# base_1.net
KiCad netlist of a schematic drawn in EAGLE
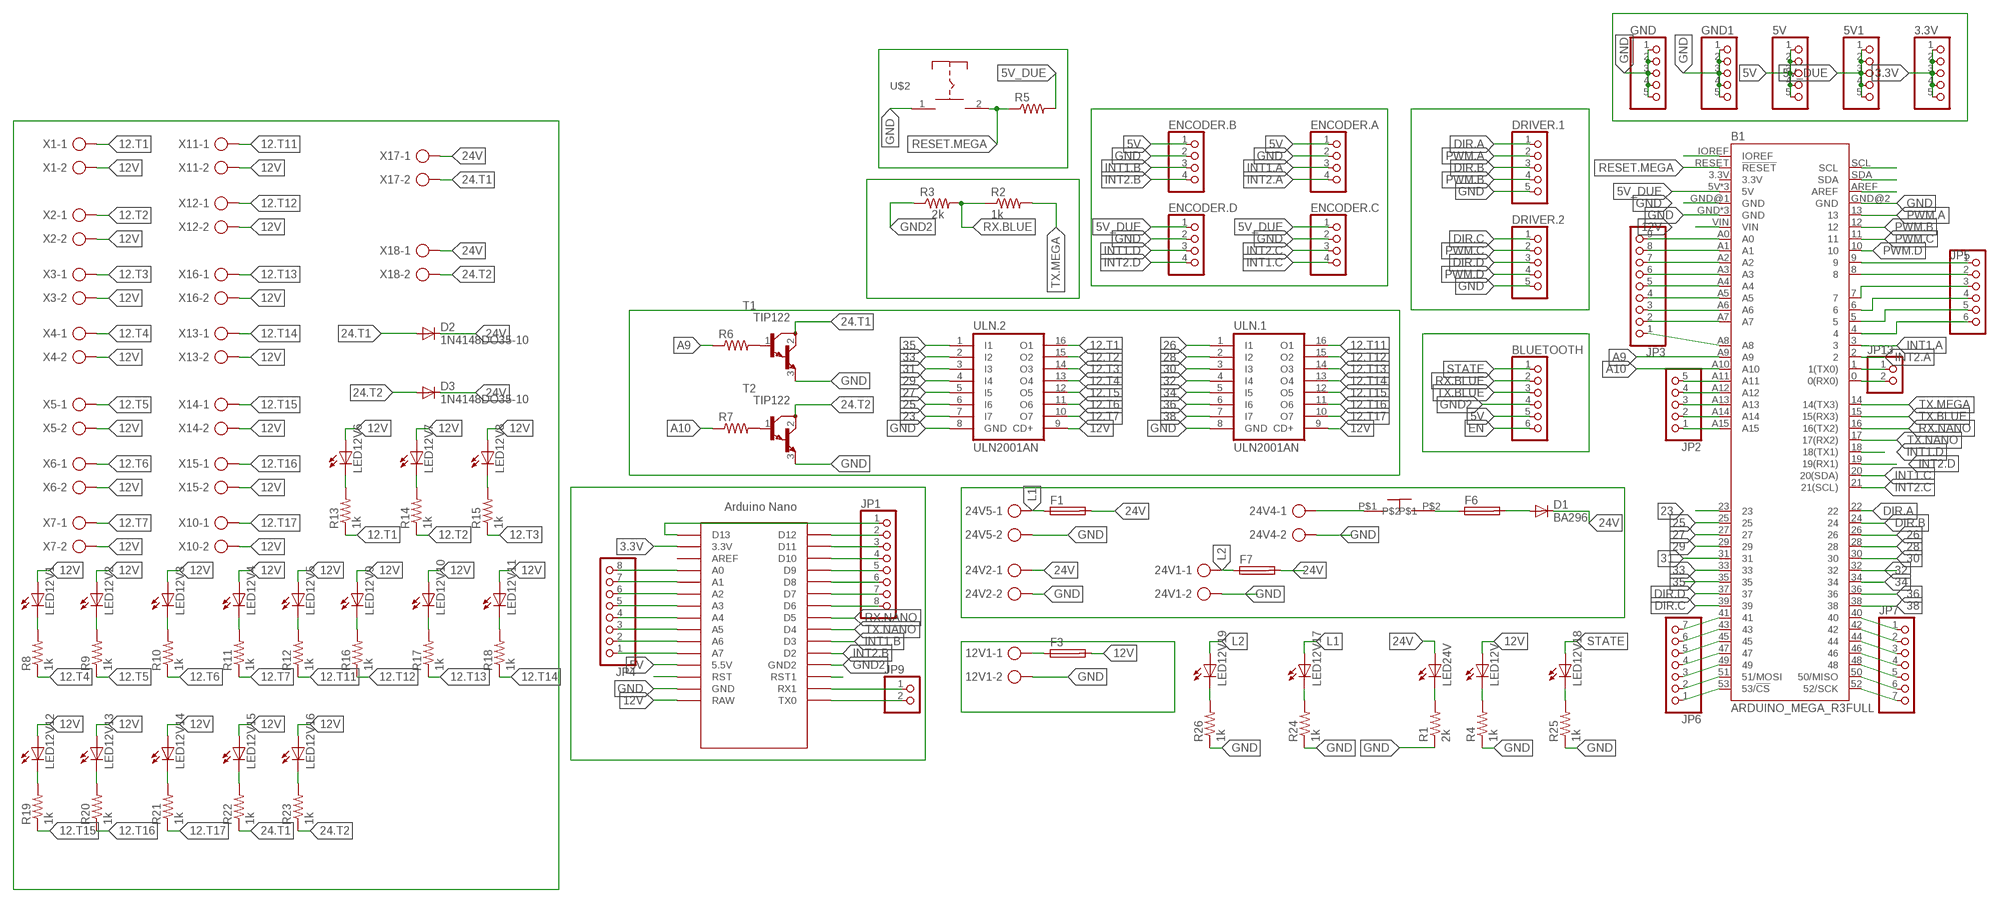
[diagram p0: schematic, sheet 1]

(export (version "E")
  (design (tool "Eeschema 10.0.6"))
  (components
    (comp (ref "3.3V")
      (value "PINHD-1X5")
      (footprint "eagle-import:1X05")
      (libsource (lib "eagle-import") (part "PINHD-1X5"))
    )
    (comp (ref "5V")
      (value "PINHD-1X5")
      (footprint "eagle-import:1X05")
      (libsource (lib "eagle-import") (part "PINHD-1X5"))
    )
    (comp (ref "5V1")
      (value "PINHD-1X5")
      (footprint "eagle-import:1X05")
      (libsource (lib "eagle-import") (part "PINHD-1X5"))
    )
    (comp (ref "12V1")
      (value "AK300/2")
      (footprint "eagle-import:AK300_2")
      (libsource (lib "eagle-import") (part "AK300/2"))
    )
    (comp (ref "24V1")
      (value "AK300/2")
      (footprint "eagle-import:AK300_2")
      (libsource (lib "eagle-import") (part "AK300/2"))
    )
    (comp (ref "24V2")
      (value "AK300/2")
      (footprint "eagle-import:AK300_2")
      (libsource (lib "eagle-import") (part "AK300/2"))
    )
    (comp (ref "24V4")
      (value "W237-113")
      (footprint "eagle-import:W237-113")
      (libsource (lib "eagle-import") (part "W237-113"))
    )
    (comp (ref "24V5")
      (value "AK300/2")
      (footprint "eagle-import:AK300_2")
      (libsource (lib "eagle-import") (part "AK300/2"))
    )
    (comp (ref "B1")
      (value "ARDUINO_MEGA_R3FULL")
      (footprint "eagle-import:ARDUINO_MEGA_NO_SILK")
      (libsource (lib "eagle-import") (part "ARDUINO_MEGA_R3FULL"))
    )
    (comp (ref "BLUETOOTH")
      (value "PINHD-1X6")
      (footprint "eagle-import:1X06")
      (libsource (lib "eagle-import") (part "PINHD-1X6"))
    )
    (comp (ref "D1")
      (value "BA296")
      (footprint "eagle-import:P2-15")
      (libsource (lib "eagle-import") (part "BA296"))
    )
    (comp (ref "D2")
      (value "1N4148DO35-10")
      (footprint "eagle-import:DO35-10")
      (libsource (lib "eagle-import") (part "1N4148DO35-10"))
    )
    (comp (ref "D3")
      (value "1N4148DO35-10")
      (footprint "eagle-import:DO35-10")
      (libsource (lib "eagle-import") (part "1N4148DO35-10"))
    )
    (comp (ref "DRIVER.1")
      (value "PINHD-1X5")
      (footprint "eagle-import:1X05")
      (libsource (lib "eagle-import") (part "PINHD-1X5"))
    )
    (comp (ref "DRIVER.2")
      (value "PINHD-1X5")
      (footprint "eagle-import:1X05")
      (libsource (lib "eagle-import") (part "PINHD-1X5"))
    )
    (comp (ref "ENCODER.A")
      (value "PINHD-1X4")
      (footprint "eagle-import:1X04")
      (libsource (lib "eagle-import") (part "PINHD-1X4"))
    )
    (comp (ref "ENCODER.B")
      (value "PINHD-1X4")
      (footprint "eagle-import:1X04")
      (libsource (lib "eagle-import") (part "PINHD-1X4"))
    )
    (comp (ref "ENCODER.C")
      (value "PINHD-1X4")
      (footprint "eagle-import:1X04")
      (libsource (lib "eagle-import") (part "PINHD-1X4"))
    )
    (comp (ref "ENCODER.D")
      (value "PINHD-1X4")
      (footprint "eagle-import:1X04")
      (libsource (lib "eagle-import") (part "PINHD-1X4"))
    )
    (comp (ref "F1")
      (value "SH22,5A")
      (footprint "eagle-import:SH22,5A")
      (fields (field (name "MPN") "0031.7701.11"))
      (libsource (lib "eagle-import") (part "SH22,5A"))
    )
    (comp (ref "F3")
      (value "SH22,5A")
      (footprint "eagle-import:SH22,5A")
      (fields (field (name "MPN") "0031.7701.11"))
      (libsource (lib "eagle-import") (part "SH22,5A"))
    )
    (comp (ref "F6")
      (value "SH22,5A")
      (footprint "eagle-import:SH22,5A")
      (fields (field (name "MPN") "0031.7701.11"))
      (libsource (lib "eagle-import") (part "SH22,5A"))
    )
    (comp (ref "F7")
      (value "SH22,5A")
      (footprint "eagle-import:SH22,5A")
      (fields (field (name "MPN") "0031.7701.11"))
      (libsource (lib "eagle-import") (part "SH22,5A"))
    )
    (comp (ref "GND")
      (value "PINHD-1X5")
      (footprint "eagle-import:1X05")
      (libsource (lib "eagle-import") (part "PINHD-1X5"))
    )
    (comp (ref "GND1")
      (value "PINHD-1X5")
      (footprint "eagle-import:1X05")
      (libsource (lib "eagle-import") (part "PINHD-1X5"))
    )
    (comp (ref "JP1")
      (value "PINHD-1X8")
      (footprint "eagle-import:1X08")
      (libsource (lib "eagle-import") (part "PINHD-1X8"))
    )
    (comp (ref "JP2")
      (value "PINHD-1X5")
      (footprint "eagle-import:1X05")
      (libsource (lib "eagle-import") (part "PINHD-1X5"))
    )
    (comp (ref "JP3")
      (value "PINHD-1X9")
      (footprint "eagle-import:1X09")
      (libsource (lib "eagle-import") (part "PINHD-1X9"))
    )
    (comp (ref "JP4")
      (value "PINHD-1X8")
      (footprint "eagle-import:1X08")
      (libsource (lib "eagle-import") (part "PINHD-1X8"))
    )
    (comp (ref "JP5")
      (value "PINHD-1X6")
      (footprint "eagle-import:1X06")
      (libsource (lib "eagle-import") (part "PINHD-1X6"))
    )
    (comp (ref "JP6")
      (value "PINHD-1X7")
      (footprint "eagle-import:1X07")
      (libsource (lib "eagle-import") (part "PINHD-1X7"))
    )
    (comp (ref "JP7")
      (value "PINHD-1X7")
      (footprint "eagle-import:1X07")
      (libsource (lib "eagle-import") (part "PINHD-1X7"))
    )
    (comp (ref "JP9")
      (value "PINHD-1X2")
      (footprint "eagle-import:1X02")
      (libsource (lib "eagle-import") (part "PINHD-1X2"))
    )
    (comp (ref "JP13")
      (value "PINHD-1X2")
      (footprint "eagle-import:1X02")
      (libsource (lib "eagle-import") (part "PINHD-1X2"))
    )
    (comp (ref "LED12V")
      (value "LED5MM")
      (footprint "eagle-import:LED5MM")
      (libsource (lib "eagle-import") (part "LED5MM"))
    )
    (comp (ref "LED12V1")
      (value "LED3MM")
      (footprint "eagle-import:LED3MM")
      (libsource (lib "eagle-import") (part "LED3MM"))
    )
    (comp (ref "LED12V2")
      (value "LED3MM")
      (footprint "eagle-import:LED3MM")
      (libsource (lib "eagle-import") (part "LED3MM"))
    )
    (comp (ref "LED12V3")
      (value "LED3MM")
      (footprint "eagle-import:LED3MM")
      (libsource (lib "eagle-import") (part "LED3MM"))
    )
    (comp (ref "LED12V4")
      (value "LED3MM")
      (footprint "eagle-import:LED3MM")
      (libsource (lib "eagle-import") (part "LED3MM"))
    )
    (comp (ref "LED12V5")
      (value "LED3MM")
      (footprint "eagle-import:LED3MM")
      (libsource (lib "eagle-import") (part "LED3MM"))
    )
    (comp (ref "LED12V6")
      (value "LED3MM")
      (footprint "eagle-import:LED3MM")
      (libsource (lib "eagle-import") (part "LED3MM"))
    )
    (comp (ref "LED12V7")
      (value "LED3MM")
      (footprint "eagle-import:LED3MM")
      (libsource (lib "eagle-import") (part "LED3MM"))
    )
    (comp (ref "LED12V8")
      (value "LED3MM")
      (footprint "eagle-import:LED3MM")
      (libsource (lib "eagle-import") (part "LED3MM"))
    )
    (comp (ref "LED12V9")
      (value "LED3MM")
      (footprint "eagle-import:LED3MM")
      (libsource (lib "eagle-import") (part "LED3MM"))
    )
    (comp (ref "LED12V10")
      (value "LED3MM")
      (footprint "eagle-import:LED3MM")
      (libsource (lib "eagle-import") (part "LED3MM"))
    )
    (comp (ref "LED12V11")
      (value "LED3MM")
      (footprint "eagle-import:LED3MM")
      (libsource (lib "eagle-import") (part "LED3MM"))
    )
    (comp (ref "LED12V12")
      (value "LED3MM")
      (footprint "eagle-import:LED3MM")
      (libsource (lib "eagle-import") (part "LED3MM"))
    )
    (comp (ref "LED12V13")
      (value "LED3MM")
      (footprint "eagle-import:LED3MM")
      (libsource (lib "eagle-import") (part "LED3MM"))
    )
    (comp (ref "LED12V14")
      (value "LED3MM")
      (footprint "eagle-import:LED3MM")
      (libsource (lib "eagle-import") (part "LED3MM"))
    )
    (comp (ref "LED12V15")
      (value "LED3MM")
      (footprint "eagle-import:LED3MM")
      (libsource (lib "eagle-import") (part "LED3MM"))
    )
    (comp (ref "LED12V16")
      (value "LED3MM")
      (footprint "eagle-import:LED3MM")
      (libsource (lib "eagle-import") (part "LED3MM"))
    )
    (comp (ref "LED12V17")
      (value "LED3MM")
      (footprint "eagle-import:LED3MM")
      (libsource (lib "eagle-import") (part "LED3MM"))
    )
    (comp (ref "LED12V18")
      (value "LED3MM")
      (footprint "eagle-import:LED3MM")
      (libsource (lib "eagle-import") (part "LED3MM"))
    )
    (comp (ref "LED12V19")
      (value "LED3MM")
      (footprint "eagle-import:LED3MM")
      (libsource (lib "eagle-import") (part "LED3MM"))
    )
    (comp (ref "LED24V")
      (value "LED5MM")
      (footprint "eagle-import:LED5MM")
      (libsource (lib "eagle-import") (part "LED5MM"))
    )
    (comp (ref "R1")
      (value "2k")
      (footprint "eagle-import:0207_10")
      (libsource (lib "eagle-import") (part "R-US_0207/10"))
    )
    (comp (ref "R2")
      (value "1k")
      (footprint "eagle-import:0204_7")
      (libsource (lib "eagle-import") (part "R-US_0204/7"))
    )
    (comp (ref "R3")
      (value "2k")
      (footprint "eagle-import:0207_10")
      (libsource (lib "eagle-import") (part "R-US_0207/10"))
    )
    (comp (ref "R4")
      (value "1k")
      (footprint "eagle-import:0207_10")
      (libsource (lib "eagle-import") (part "R-US_0207/10"))
    )
    (comp (ref "R5")
      (value "R-US_0207/12")
      (footprint "eagle-import:0207_12")
      (libsource (lib "eagle-import") (part "R-US_0207/12"))
    )
    (comp (ref "R6")
      (value "R-US_0204/5")
      (footprint "eagle-import:0204_5")
      (libsource (lib "eagle-import") (part "R-US_0204/5"))
    )
    (comp (ref "R7")
      (value "R-US_0204/5")
      (footprint "eagle-import:0204_5")
      (libsource (lib "eagle-import") (part "R-US_0204/5"))
    )
    (comp (ref "R8")
      (value "1k")
      (footprint "eagle-import:0204_5")
      (libsource (lib "eagle-import") (part "R-US_0204/5"))
    )
    (comp (ref "R9")
      (value "1k")
      (footprint "eagle-import:0204_5")
      (libsource (lib "eagle-import") (part "R-US_0204/5"))
    )
    (comp (ref "R10")
      (value "1k")
      (footprint "eagle-import:0204_5")
      (libsource (lib "eagle-import") (part "R-US_0204/5"))
    )
    (comp (ref "R11")
      (value "1k")
      (footprint "eagle-import:0204_5")
      (libsource (lib "eagle-import") (part "R-US_0204/5"))
    )
    (comp (ref "R12")
      (value "1k")
      (footprint "eagle-import:0204_5")
      (libsource (lib "eagle-import") (part "R-US_0204/5"))
    )
    (comp (ref "R13")
      (value "1k")
      (footprint "eagle-import:0204_5")
      (libsource (lib "eagle-import") (part "R-US_0204/5"))
    )
    (comp (ref "R14")
      (value "1k")
      (footprint "eagle-import:0204_5")
      (libsource (lib "eagle-import") (part "R-US_0204/5"))
    )
    (comp (ref "R15")
      (value "1k")
      (footprint "eagle-import:0204_5")
      (libsource (lib "eagle-import") (part "R-US_0204/5"))
    )
    (comp (ref "R16")
      (value "1k")
      (footprint "eagle-import:0204_5")
      (libsource (lib "eagle-import") (part "R-US_0204/5"))
    )
    (comp (ref "R17")
      (value "1k")
      (footprint "eagle-import:0204_5")
      (libsource (lib "eagle-import") (part "R-US_0204/5"))
    )
    (comp (ref "R18")
      (value "1k")
      (footprint "eagle-import:0204_5")
      (libsource (lib "eagle-import") (part "R-US_0204/5"))
    )
    (comp (ref "R19")
      (value "1k")
      (footprint "eagle-import:0204_5")
      (libsource (lib "eagle-import") (part "R-US_0204/5"))
    )
    (comp (ref "R20")
      (value "1k")
      (footprint "eagle-import:0204_5")
      (libsource (lib "eagle-import") (part "R-US_0204/5"))
    )
    (comp (ref "R21")
      (value "1k")
      (footprint "eagle-import:0204_5")
      (libsource (lib "eagle-import") (part "R-US_0204/5"))
    )
    (comp (ref "R22")
      (value "1k")
      (footprint "eagle-import:0204_5")
      (libsource (lib "eagle-import") (part "R-US_0204/5"))
    )
    (comp (ref "R23")
      (value "1k")
      (footprint "eagle-import:0204_5")
      (libsource (lib "eagle-import") (part "R-US_0204/5"))
    )
    (comp (ref "R24")
      (value "1k")
      (footprint "eagle-import:0204_5")
      (libsource (lib "eagle-import") (part "R-US_0204/5"))
    )
    (comp (ref "R25")
      (value "1k")
      (footprint "eagle-import:0204_5")
      (libsource (lib "eagle-import") (part "R-US_0204/5"))
    )
    (comp (ref "R26")
      (value "1k")
      (footprint "eagle-import:0204_5")
      (libsource (lib "eagle-import") (part "R-US_0204/5"))
    )
    (comp (ref "T1")
      (value "TIP122")
      (footprint "eagle-import:TO220")
      (libsource (lib "eagle-import") (part "TIP122"))
    )
    (comp (ref "T2")
      (value "TIP122")
      (footprint "eagle-import:TO220")
      (libsource (lib "eagle-import") (part "TIP122"))
    )
    (comp (ref "U$1")
      (value "NANO")
      (footprint "eagle-import:NANO")
      (libsource (lib "eagle-import") (part "NANO"))
    )
    (comp (ref "U$2")
      (value "PUSHBOTTON")
      (footprint "eagle-import:PUSHBOTTON")
      (libsource (lib "eagle-import") (part "PUSHBOTTON"))
    )
    (comp (ref "U$3")
      (value "ON_OFF")
      (footprint "eagle-import:ON_OFF")
      (libsource (lib "eagle-import") (part "ON_OFF"))
    )
    (comp (ref "ULN.1")
      (value "ULN2001AN")
      (footprint "eagle-import:DIL16")
      (libsource (lib "eagle-import") (part "ULN2001AN"))
    )
    (comp (ref "ULN.2")
      (value "ULN2001AN")
      (footprint "eagle-import:DIL16")
      (libsource (lib "eagle-import") (part "ULN2001AN"))
    )
    (comp (ref "X1")
      (value "AK300/2")
      (footprint "eagle-import:AK300_2")
      (libsource (lib "eagle-import") (part "AK300/2"))
    )
    (comp (ref "X2")
      (value "AK300/2")
      (footprint "eagle-import:AK300_2")
      (libsource (lib "eagle-import") (part "AK300/2"))
    )
    (comp (ref "X3")
      (value "AK300/2")
      (footprint "eagle-import:AK300_2")
      (libsource (lib "eagle-import") (part "AK300/2"))
    )
    (comp (ref "X4")
      (value "AK300/2")
      (footprint "eagle-import:AK300_2")
      (libsource (lib "eagle-import") (part "AK300/2"))
    )
    (comp (ref "X5")
      (value "AK300/2")
      (footprint "eagle-import:AK300_2")
      (libsource (lib "eagle-import") (part "AK300/2"))
    )
    (comp (ref "X6")
      (value "AK300/2")
      (footprint "eagle-import:AK300_2")
      (libsource (lib "eagle-import") (part "AK300/2"))
    )
    (comp (ref "X7")
      (value "AK300/2")
      (footprint "eagle-import:AK300_2")
      (libsource (lib "eagle-import") (part "AK300/2"))
    )
    (comp (ref "X10")
      (value "AK300/2")
      (footprint "eagle-import:AK300_2")
      (libsource (lib "eagle-import") (part "AK300/2"))
    )
    (comp (ref "X11")
      (value "AK300/2")
      (footprint "eagle-import:AK300_2")
      (libsource (lib "eagle-import") (part "AK300/2"))
    )
    (comp (ref "X12")
      (value "AK300/2")
      (footprint "eagle-import:AK300_2")
      (libsource (lib "eagle-import") (part "AK300/2"))
    )
    (comp (ref "X13")
      (value "AK300/2")
      (footprint "eagle-import:AK300_2")
      (libsource (lib "eagle-import") (part "AK300/2"))
    )
    (comp (ref "X14")
      (value "AK300/2")
      (footprint "eagle-import:AK300_2")
      (libsource (lib "eagle-import") (part "AK300/2"))
    )
    (comp (ref "X15")
      (value "AK300/2")
      (footprint "eagle-import:AK300_2")
      (libsource (lib "eagle-import") (part "AK300/2"))
    )
    (comp (ref "X16")
      (value "AK300/2")
      (footprint "eagle-import:AK300_2")
      (libsource (lib "eagle-import") (part "AK300/2"))
    )
    (comp (ref "X17")
      (value "AK300/2")
      (footprint "eagle-import:AK300_2")
      (libsource (lib "eagle-import") (part "AK300/2"))
    )
    (comp (ref "X18")
      (value "AK300/2")
      (footprint "eagle-import:AK300_2")
      (libsource (lib "eagle-import") (part "AK300/2"))
    )
  )
  (nets
    (net (code "1") (name "3.3V") (class "Default")
      (node (ref "3.3V") (pin "1") (pinfunction "1_1") (pintype "passive"))
      (node (ref "3.3V") (pin "2") (pinfunction "2_2") (pintype "passive"))
      (node (ref "3.3V") (pin "3") (pinfunction "3_3") (pintype "passive"))
      (node (ref "3.3V") (pin "4") (pinfunction "4_4") (pintype "passive"))
      (node (ref "3.3V") (pin "5") (pinfunction "5_5") (pintype "passive"))
      (node (ref "U$1") (pin "3.3V") (pinfunction "3.3V_3.3V") (pintype "bidirectional"))
    )
    (net (code "2") (name "5V") (class "Default")
      (node (ref "5V") (pin "1") (pinfunction "1_1") (pintype "passive"))
      (node (ref "5V") (pin "2") (pinfunction "2_2") (pintype "passive"))
      (node (ref "5V") (pin "3") (pinfunction "3_3") (pintype "passive"))
      (node (ref "5V") (pin "4") (pinfunction "4_4") (pintype "passive"))
      (node (ref "5V") (pin "5") (pinfunction "5_5") (pintype "passive"))
      (node (ref "BLUETOOTH") (pin "5") (pinfunction "5_5") (pintype "passive"))
      (node (ref "ENCODER.A") (pin "1") (pinfunction "1_1") (pintype "passive"))
      (node (ref "ENCODER.B") (pin "1") (pinfunction "1_1") (pintype "passive"))
      (node (ref "U$1") (pin "5V") (pinfunction "5.5V_5V") (pintype "bidirectional"))
    )
    (net (code "3") (name "5V_DUE") (class "Default")
      (node (ref "5V1") (pin "1") (pinfunction "1_1") (pintype "passive"))
      (node (ref "5V1") (pin "2") (pinfunction "2_2") (pintype "passive"))
      (node (ref "5V1") (pin "3") (pinfunction "3_3") (pintype "passive"))
      (node (ref "5V1") (pin "4") (pinfunction "4_4") (pintype "passive"))
      (node (ref "5V1") (pin "5") (pinfunction "5_5") (pintype "passive"))
      (node (ref "B1") (pin "5V") (pinfunction "5V_5V") (pintype "bidirectional"))
      (node (ref "B1") (pin "5V@1") (pinfunction "5V_5V@1") (pintype "bidirectional"))
      (node (ref "B1") (pin "5V@2") (pinfunction "5V_5V@2") (pintype "bidirectional"))
      (node (ref "ENCODER.C") (pin "1") (pinfunction "1_1") (pintype "passive"))
      (node (ref "ENCODER.D") (pin "1") (pinfunction "1_1") (pintype "passive"))
      (node (ref "R5") (pin "2") (pinfunction "2_2") (pintype "passive"))
    )
    (net (code "4") (name "12.T1") (class "Default")
      (node (ref "R13") (pin "1") (pinfunction "1_1") (pintype "passive"))
      (node (ref "ULN.2") (pin "16") (pinfunction "O1_16") (pintype "open_collector"))
      (node (ref "X1") (pin "1") (pinfunction "KL_1") (pintype "passive"))
    )
    (net (code "5") (name "12.T2") (class "Default")
      (node (ref "R14") (pin "1") (pinfunction "1_1") (pintype "passive"))
      (node (ref "ULN.2") (pin "15") (pinfunction "O2_15") (pintype "open_collector"))
      (node (ref "X2") (pin "1") (pinfunction "KL_1") (pintype "passive"))
    )
    (net (code "6") (name "12.T3") (class "Default")
      (node (ref "R15") (pin "1") (pinfunction "1_1") (pintype "passive"))
      (node (ref "ULN.2") (pin "14") (pinfunction "O3_14") (pintype "open_collector"))
      (node (ref "X3") (pin "1") (pinfunction "KL_1") (pintype "passive"))
    )
    (net (code "7") (name "12.T4") (class "Default")
      (node (ref "R8") (pin "1") (pinfunction "1_1") (pintype "passive"))
      (node (ref "ULN.2") (pin "13") (pinfunction "O4_13") (pintype "open_collector"))
      (node (ref "X4") (pin "1") (pinfunction "KL_1") (pintype "passive"))
    )
    (net (code "8") (name "12.T5") (class "Default")
      (node (ref "R9") (pin "1") (pinfunction "1_1") (pintype "passive"))
      (node (ref "ULN.2") (pin "12") (pinfunction "O5_12") (pintype "open_collector"))
      (node (ref "X5") (pin "1") (pinfunction "KL_1") (pintype "passive"))
    )
    (net (code "9") (name "12.T6") (class "Default")
      (node (ref "R10") (pin "1") (pinfunction "1_1") (pintype "passive"))
      (node (ref "ULN.2") (pin "11") (pinfunction "O6_11") (pintype "open_collector"))
      (node (ref "X6") (pin "1") (pinfunction "KL_1") (pintype "passive"))
    )
    (net (code "10") (name "12.T7") (class "Default")
      (node (ref "R11") (pin "1") (pinfunction "1_1") (pintype "passive"))
      (node (ref "ULN.2") (pin "10") (pinfunction "O7_10") (pintype "open_collector"))
      (node (ref "X7") (pin "1") (pinfunction "KL_1") (pintype "passive"))
    )
    (net (code "11") (name "12.T11") (class "Default")
      (node (ref "R12") (pin "1") (pinfunction "1_1") (pintype "passive"))
      (node (ref "ULN.1") (pin "16") (pinfunction "O1_16") (pintype "open_collector"))
      (node (ref "X11") (pin "1") (pinfunction "KL_1") (pintype "passive"))
    )
    (net (code "12") (name "12.T12") (class "Default")
      (node (ref "R16") (pin "1") (pinfunction "1_1") (pintype "passive"))
      (node (ref "ULN.1") (pin "15") (pinfunction "O2_15") (pintype "open_collector"))
      (node (ref "X12") (pin "1") (pinfunction "KL_1") (pintype "passive"))
    )
    (net (code "13") (name "12.T13") (class "Default")
      (node (ref "R17") (pin "1") (pinfunction "1_1") (pintype "passive"))
      (node (ref "ULN.1") (pin "14") (pinfunction "O3_14") (pintype "open_collector"))
      (node (ref "X16") (pin "1") (pinfunction "KL_1") (pintype "passive"))
    )
    (net (code "14") (name "12.T14") (class "Default")
      (node (ref "R18") (pin "1") (pinfunction "1_1") (pintype "passive"))
      (node (ref "ULN.1") (pin "13") (pinfunction "O4_13") (pintype "open_collector"))
      (node (ref "X13") (pin "1") (pinfunction "KL_1") (pintype "passive"))
    )
    (net (code "15") (name "12.T15") (class "Default")
      (node (ref "R19") (pin "1") (pinfunction "1_1") (pintype "passive"))
      (node (ref "ULN.1") (pin "12") (pinfunction "O5_12") (pintype "open_collector"))
      (node (ref "X14") (pin "1") (pinfunction "KL_1") (pintype "passive"))
    )
    (net (code "16") (name "12.T16") (class "Default")
      (node (ref "R20") (pin "1") (pinfunction "1_1") (pintype "passive"))
      (node (ref "ULN.1") (pin "11") (pinfunction "O6_11") (pintype "open_collector"))
      (node (ref "X15") (pin "1") (pinfunction "KL_1") (pintype "passive"))
    )
    (net (code "17") (name "12.T17") (class "Default")
      (node (ref "R21") (pin "1") (pinfunction "1_1") (pintype "passive"))
      (node (ref "ULN.1") (pin "10") (pinfunction "O7_10") (pintype "open_collector"))
      (node (ref "X10") (pin "1") (pinfunction "KL_1") (pintype "passive"))
    )
    (net (code "18") (name "12V") (class "Default")
      (node (ref "B1") (pin "VIN") (pinfunction "VIN_VIN") (pintype "bidirectional"))
      (node (ref "F3") (pin "2") (pinfunction "2_2") (pintype "passive"))
      (node (ref "LED12V") (pin "A") (pinfunction "A_A") (pintype "passive"))
      (node (ref "LED12V1") (pin "A") (pinfunction "A_A") (pintype "passive"))
      (node (ref "LED12V10") (pin "A") (pinfunction "A_A") (pintype "passive"))
      (node (ref "LED12V11") (pin "A") (pinfunction "A_A") (pintype "passive"))
      (node (ref "LED12V12") (pin "A") (pinfunction "A_A") (pintype "passive"))
      (node (ref "LED12V13") (pin "A") (pinfunction "A_A") (pintype "passive"))
      (node (ref "LED12V14") (pin "A") (pinfunction "A_A") (pintype "passive"))
      (node (ref "LED12V15") (pin "A") (pinfunction "A_A") (pintype "passive"))
      (node (ref "LED12V16") (pin "A") (pinfunction "A_A") (pintype "passive"))
      (node (ref "LED12V2") (pin "A") (pinfunction "A_A") (pintype "passive"))
      (node (ref "LED12V3") (pin "A") (pinfunction "A_A") (pintype "passive"))
      (node (ref "LED12V4") (pin "A") (pinfunction "A_A") (pintype "passive"))
      (node (ref "LED12V5") (pin "A") (pinfunction "A_A") (pintype "passive"))
      (node (ref "LED12V6") (pin "A") (pinfunction "A_A") (pintype "passive"))
      (node (ref "LED12V7") (pin "A") (pinfunction "A_A") (pintype "passive"))
      (node (ref "LED12V8") (pin "A") (pinfunction "A_A") (pintype "passive"))
      (node (ref "LED12V9") (pin "A") (pinfunction "A_A") (pintype "passive"))
      (node (ref "U$1") (pin "RAW") (pinfunction "RAW_RAW") (pintype "bidirectional"))
      (node (ref "ULN.1") (pin "9") (pinfunction "CD+_9") (pintype "passive"))
      (node (ref "ULN.2") (pin "9") (pinfunction "CD+_9") (pintype "passive"))
      (node (ref "X1") (pin "2") (pinfunction "KL_2") (pintype "passive"))
      (node (ref "X10") (pin "2") (pinfunction "KL_2") (pintype "passive"))
      (node (ref "X11") (pin "2") (pinfunction "KL_2") (pintype "passive"))
      (node (ref "X12") (pin "2") (pinfunction "KL_2") (pintype "passive"))
      (node (ref "X13") (pin "2") (pinfunction "KL_2") (pintype "passive"))
      (node (ref "X14") (pin "2") (pinfunction "KL_2") (pintype "passive"))
      (node (ref "X15") (pin "2") (pinfunction "KL_2") (pintype "passive"))
      (node (ref "X16") (pin "2") (pinfunction "KL_2") (pintype "passive"))
      (node (ref "X2") (pin "2") (pinfunction "KL_2") (pintype "passive"))
      (node (ref "X3") (pin "2") (pinfunction "KL_2") (pintype "passive"))
      (node (ref "X4") (pin "2") (pinfunction "KL_2") (pintype "passive"))
      (node (ref "X5") (pin "2") (pinfunction "KL_2") (pintype "passive"))
      (node (ref "X6") (pin "2") (pinfunction "KL_2") (pintype "passive"))
      (node (ref "X7") (pin "2") (pinfunction "KL_2") (pintype "passive"))
    )
    (net (code "19") (name "23") (class "Default")
      (node (ref "B1") (pin "23") (pinfunction "23_23") (pintype "bidirectional"))
      (node (ref "ULN.2") (pin "7") (pinfunction "I7_7") (pintype "input"))
    )
    (net (code "20") (name "24.T1") (class "Default")
      (node (ref "D2") (pin "A") (pinfunction "A_A") (pintype "passive"))
      (node (ref "R22") (pin "1") (pinfunction "1_1") (pintype "passive"))
      (node (ref "T1") (pin "2") (pinfunction "C_2") (pintype "passive"))
      (node (ref "X17") (pin "2") (pinfunction "KL_2") (pintype "passive"))
    )
    (net (code "21") (name "24.T2") (class "Default")
      (node (ref "D3") (pin "A") (pinfunction "A_A") (pintype "passive"))
      (node (ref "R23") (pin "1") (pinfunction "1_1") (pintype "passive"))
      (node (ref "T2") (pin "2") (pinfunction "C_2") (pintype "passive"))
      (node (ref "X18") (pin "2") (pinfunction "KL_2") (pintype "passive"))
    )
    (net (code "22") (name "24V") (class "Default")
      (node (ref "24V2") (pin "1") (pinfunction "KL_1") (pintype "passive"))
      (node (ref "D1") (pin "C") (pinfunction "C_C") (pintype "passive"))
      (node (ref "D2") (pin "C") (pinfunction "C_C") (pintype "passive"))
      (node (ref "D3") (pin "C") (pinfunction "C_C") (pintype "passive"))
      (node (ref "F1") (pin "2") (pinfunction "2_2") (pintype "passive"))
      (node (ref "F7") (pin "2") (pinfunction "2_2") (pintype "passive"))
      (node (ref "LED24V") (pin "A") (pinfunction "A_A") (pintype "passive"))
      (node (ref "X17") (pin "1") (pinfunction "KL_1") (pintype "passive"))
      (node (ref "X18") (pin "1") (pinfunction "KL_1") (pintype "passive"))
    )
    (net (code "23") (name "25") (class "Default")
      (node (ref "B1") (pin "25") (pinfunction "25_25") (pintype "bidirectional"))
      (node (ref "ULN.2") (pin "6") (pinfunction "I6_6") (pintype "input"))
    )
    (net (code "24") (name "26") (class "Default")
      (node (ref "B1") (pin "26") (pinfunction "26_26") (pintype "bidirectional"))
      (node (ref "ULN.1") (pin "1") (pinfunction "I1_1") (pintype "input"))
    )
    (net (code "25") (name "27") (class "Default")
      (node (ref "B1") (pin "27") (pinfunction "27_27") (pintype "bidirectional"))
      (node (ref "ULN.2") (pin "5") (pinfunction "I5_5") (pintype "input"))
    )
    (net (code "26") (name "28") (class "Default")
      (node (ref "B1") (pin "28") (pinfunction "28_28") (pintype "bidirectional"))
      (node (ref "ULN.1") (pin "2") (pinfunction "I2_2") (pintype "input"))
    )
    (net (code "27") (name "29") (class "Default")
      (node (ref "B1") (pin "29") (pinfunction "29_29") (pintype "bidirectional"))
      (node (ref "ULN.2") (pin "4") (pinfunction "I4_4") (pintype "input"))
    )
    (net (code "28") (name "30") (class "Default")
      (node (ref "B1") (pin "30") (pinfunction "30_30") (pintype "bidirectional"))
      (node (ref "ULN.1") (pin "3") (pinfunction "I3_3") (pintype "input"))
    )
    (net (code "29") (name "31") (class "Default")
      (node (ref "B1") (pin "31") (pinfunction "31_31") (pintype "bidirectional"))
      (node (ref "ULN.2") (pin "3") (pinfunction "I3_3") (pintype "input"))
    )
    (net (code "30") (name "32") (class "Default")
      (node (ref "B1") (pin "32") (pinfunction "32_32") (pintype "bidirectional"))
      (node (ref "ULN.1") (pin "4") (pinfunction "I4_4") (pintype "input"))
    )
    (net (code "31") (name "33") (class "Default")
      (node (ref "B1") (pin "33") (pinfunction "33_33") (pintype "bidirectional"))
      (node (ref "ULN.2") (pin "2") (pinfunction "I2_2") (pintype "input"))
    )
    (net (code "32") (name "34") (class "Default")
      (node (ref "B1") (pin "34") (pinfunction "34_34") (pintype "bidirectional"))
      (node (ref "ULN.1") (pin "5") (pinfunction "I5_5") (pintype "input"))
    )
    (net (code "33") (name "35") (class "Default")
      (node (ref "B1") (pin "35") (pinfunction "35_35") (pintype "bidirectional"))
      (node (ref "ULN.2") (pin "1") (pinfunction "I1_1") (pintype "input"))
    )
    (net (code "34") (name "36") (class "Default")
      (node (ref "B1") (pin "36") (pinfunction "36_36") (pintype "bidirectional"))
      (node (ref "ULN.1") (pin "6") (pinfunction "I6_6") (pintype "input"))
    )
    (net (code "35") (name "38") (class "Default")
      (node (ref "B1") (pin "38") (pinfunction "38_38") (pintype "bidirectional"))
      (node (ref "ULN.1") (pin "7") (pinfunction "I7_7") (pintype "input"))
    )
    (net (code "36") (name "A9") (class "Default")
      (node (ref "B1") (pin "A9") (pinfunction "A9_A9") (pintype "bidirectional"))
      (node (ref "R6") (pin "1") (pinfunction "1_1") (pintype "passive"))
    )
    (net (code "37") (name "A10") (class "Default")
      (node (ref "B1") (pin "A10") (pinfunction "A10_A10") (pintype "bidirectional"))
      (node (ref "R7") (pin "1") (pinfunction "1_1") (pintype "passive"))
    )
    (net (code "38") (name "DIR.A") (class "Default")
      (node (ref "B1") (pin "22") (pinfunction "22_22") (pintype "bidirectional"))
      (node (ref "DRIVER.1") (pin "1") (pinfunction "1_1") (pintype "passive"))
    )
    (net (code "39") (name "DIR.B") (class "Default")
      (node (ref "B1") (pin "24") (pinfunction "24_24") (pintype "bidirectional"))
      (node (ref "DRIVER.1") (pin "3") (pinfunction "3_3") (pintype "passive"))
    )
    (net (code "40") (name "DIR.C") (class "Default")
      (node (ref "B1") (pin "39") (pinfunction "39_39") (pintype "bidirectional"))
      (node (ref "DRIVER.2") (pin "1") (pinfunction "1_1") (pintype "passive"))
    )
    (net (code "41") (name "DIR.D") (class "Default")
      (node (ref "B1") (pin "37") (pinfunction "37_37") (pintype "bidirectional"))
      (node (ref "DRIVER.2") (pin "3") (pinfunction "3_3") (pintype "passive"))
    )
    (net (code "42") (name "EN") (class "Default")
      (node (ref "BLUETOOTH") (pin "6") (pinfunction "6_6") (pintype "passive"))
    )
    (net (code "43") (name "GND") (class "Default")
      (node (ref "12V1") (pin "2") (pinfunction "KL_2") (pintype "passive"))
      (node (ref "24V1") (pin "2") (pinfunction "KL_2") (pintype "passive"))
      (node (ref "24V2") (pin "2") (pinfunction "KL_2") (pintype "passive"))
      (node (ref "24V4") (pin "2") (pinfunction "KL_2") (pintype "passive"))
      (node (ref "24V5") (pin "2") (pinfunction "KL_2") (pintype "passive"))
      (node (ref "B1") (pin "GND") (pinfunction "GND_GND") (pintype "bidirectional"))
      (node (ref "B1") (pin "GND@1") (pinfunction "GND_GND@1") (pintype "bidirectional"))
      (node (ref "B1") (pin "GND@2") (pinfunction "GND_GND@2") (pintype "bidirectional"))
      (node (ref "B1") (pin "GND@3") (pinfunction "GND_GND@3") (pintype "bidirectional"))
      (node (ref "B1") (pin "GND@4") (pinfunction "GND_GND@4") (pintype "bidirectional"))
      (node (ref "DRIVER.1") (pin "5") (pinfunction "5_5") (pintype "passive"))
      (node (ref "DRIVER.2") (pin "5") (pinfunction "5_5") (pintype "passive"))
      (node (ref "ENCODER.A") (pin "2") (pinfunction "2_2") (pintype "passive"))
      (node (ref "ENCODER.B") (pin "2") (pinfunction "2_2") (pintype "passive"))
      (node (ref "ENCODER.C") (pin "2") (pinfunction "2_2") (pintype "passive"))
      (node (ref "ENCODER.D") (pin "2") (pinfunction "2_2") (pintype "passive"))
      (node (ref "GND") (pin "1") (pinfunction "1_1") (pintype "passive"))
      (node (ref "GND") (pin "2") (pinfunction "2_2") (pintype "passive"))
      (node (ref "GND") (pin "3") (pinfunction "3_3") (pintype "passive"))
      (node (ref "GND") (pin "4") (pinfunction "4_4") (pintype "passive"))
      (node (ref "GND") (pin "5") (pinfunction "5_5") (pintype "passive"))
      (node (ref "GND1") (pin "1") (pinfunction "1_1") (pintype "passive"))
      (node (ref "GND1") (pin "2") (pinfunction "2_2") (pintype "passive"))
      (node (ref "GND1") (pin "3") (pinfunction "3_3") (pintype "passive"))
      (node (ref "GND1") (pin "4") (pinfunction "4_4") (pintype "passive"))
      (node (ref "GND1") (pin "5") (pinfunction "5_5") (pintype "passive"))
      (node (ref "R1") (pin "1") (pinfunction "1_1") (pintype "passive"))
      (node (ref "R24") (pin "1") (pinfunction "1_1") (pintype "passive"))
      (node (ref "R25") (pin "1") (pinfunction "1_1") (pintype "passive"))
      (node (ref "R26") (pin "1") (pinfunction "1_1") (pintype "passive"))
      (node (ref "R4") (pin "1") (pinfunction "1_1") (pintype "passive"))
      (node (ref "T1") (pin "3") (pinfunction "E_3") (pintype "passive"))
      (node (ref "T2") (pin "3") (pinfunction "E_3") (pintype "passive"))
      (node (ref "U$1") (pin "GND") (pinfunction "GND_GND") (pintype "bidirectional"))
      (node (ref "U$2") (pin "1") (pinfunction "1_1") (pintype "bidirectional"))
      (node (ref "ULN.1") (pin "8") (pinfunction "GND_8") (pintype "power_in"))
      (node (ref "ULN.2") (pin "8") (pinfunction "GND_8") (pintype "power_in"))
    )
    (net (code "44") (name "GND2") (class "Default")
      (node (ref "BLUETOOTH") (pin "4") (pinfunction "4_4") (pintype "passive"))
      (node (ref "R3") (pin "1") (pinfunction "1_1") (pintype "passive"))
      (node (ref "U$1") (pin "GND1") (pinfunction "GND2_GND1") (pintype "bidirectional"))
    )
    (net (code "45") (name "INT1.A") (class "Default")
      (node (ref "B1") (pin "3") (pinfunction "3_3") (pintype "bidirectional"))
      (node (ref "ENCODER.A") (pin "3") (pinfunction "3_3") (pintype "passive"))
    )
    (net (code "46") (name "INT1.B") (class "Default")
      (node (ref "ENCODER.B") (pin "3") (pinfunction "3_3") (pintype "passive"))
      (node (ref "U$1") (pin "D3") (pinfunction "D3_D3") (pintype "bidirectional"))
    )
    (net (code "47") (name "INT1.C") (class "Default")
      (node (ref "B1") (pin "20") (pinfunction "20(SDA)_20") (pintype "bidirectional"))
      (node (ref "ENCODER.C") (pin "4") (pinfunction "4_4") (pintype "passive"))
    )
    (net (code "48") (name "INT1.D") (class "Default")
      (node (ref "B1") (pin "18") (pinfunction "18(TX1)_18") (pintype "bidirectional"))
      (node (ref "ENCODER.D") (pin "3") (pinfunction "3_3") (pintype "passive"))
    )
    (net (code "49") (name "INT2.A") (class "Default")
      (node (ref "B1") (pin "2") (pinfunction "2_2") (pintype "bidirectional"))
      (node (ref "ENCODER.A") (pin "4") (pinfunction "4_4") (pintype "passive"))
    )
    (net (code "50") (name "INT2.B") (class "Default")
      (node (ref "ENCODER.B") (pin "4") (pinfunction "4_4") (pintype "passive"))
      (node (ref "U$1") (pin "D2") (pinfunction "D2_D2") (pintype "bidirectional"))
    )
    (net (code "51") (name "INT2.C") (class "Default")
      (node (ref "B1") (pin "21") (pinfunction "21(SCL)_21") (pintype "bidirectional"))
      (node (ref "ENCODER.C") (pin "3") (pinfunction "3_3") (pintype "passive"))
    )
    (net (code "52") (name "INT2.D") (class "Default")
      (node (ref "B1") (pin "19") (pinfunction "19(RX1)_19") (pintype "bidirectional"))
      (node (ref "ENCODER.D") (pin "4") (pinfunction "4_4") (pintype "passive"))
    )
    (net (code "53") (name "L1") (class "Default")
      (node (ref "24V5") (pin "1") (pinfunction "KL_1") (pintype "passive"))
      (node (ref "F1") (pin "1") (pinfunction "1_1") (pintype "passive"))
      (node (ref "LED12V17") (pin "A") (pinfunction "A_A") (pintype "passive"))
    )
    (net (code "54") (name "L2") (class "Default")
      (node (ref "24V1") (pin "1") (pinfunction "KL_1") (pintype "passive"))
      (node (ref "F7") (pin "1") (pinfunction "1_1") (pintype "passive"))
      (node (ref "LED12V19") (pin "A") (pinfunction "A_A") (pintype "passive"))
    )
    (net (code "55") (name "Net-(12V1A-KL)") (class "Default")
      (node (ref "12V1") (pin "1") (pinfunction "KL_1") (pintype "passive"))
      (node (ref "F3") (pin "1") (pinfunction "1_1") (pintype "passive"))
    )
    (net (code "56") (name "Net-(24V4A-KL)") (class "Default")
      (node (ref "24V4") (pin "1") (pinfunction "KL_1") (pintype "passive"))
      (node (ref "U$3") (pin "P$1") (pinfunction "P$1_P$1") (pintype "bidirectional"))
    )
    (net (code "57") (name "Net-(B1-0(RX0))") (class "Default")
      (node (ref "B1") (pin "0") (pinfunction "0(RX0)_0") (pintype "bidirectional"))
      (node (ref "JP13") (pin "2") (pinfunction "2_2") (pintype "passive"))
    )
    (net (code "58") (name "Net-(B1-1(TX0))") (class "Default")
      (node (ref "B1") (pin "1") (pinfunction "1(TX0)_1") (pintype "bidirectional"))
      (node (ref "JP13") (pin "1") (pinfunction "1_1") (pintype "passive"))
    )
    (net (code "59") (name "Net-(B1-50{slash}MISO)") (class "Default")
      (node (ref "B1") (pin "50") (pinfunction "50/MISO_50") (pintype "bidirectional"))
      (node (ref "JP7") (pin "6") (pinfunction "6_6") (pintype "passive"))
    )
    (net (code "60") (name "Net-(B1-51{slash}MOSI)") (class "Default")
      (node (ref "B1") (pin "51") (pinfunction "51/MOSI_51") (pintype "bidirectional"))
      (node (ref "JP6") (pin "2") (pinfunction "2_2") (pintype "passive"))
    )
    (net (code "61") (name "Net-(B1-52{slash}SCK)") (class "Default")
      (node (ref "B1") (pin "52") (pinfunction "52/SCK_52") (pintype "bidirectional"))
      (node (ref "JP7") (pin "7") (pinfunction "7_7") (pintype "passive"))
    )
    (net (code "62") (name "Net-(B1-53{slash}~{CS})") (class "Default")
      (node (ref "B1") (pin "53") (pinfunction "53/~{CS}_53") (pintype "bidirectional"))
      (node (ref "JP6") (pin "1") (pinfunction "1_1") (pintype "passive"))
    )
    (net (code "63") (name "Net-(B1-Pad4)") (class "Default")
      (node (ref "B1") (pin "4") (pinfunction "4_4") (pintype "bidirectional"))
      (node (ref "JP5") (pin "6") (pinfunction "6_6") (pintype "passive"))
    )
    (net (code "64") (name "Net-(B1-Pad5)") (class "Default")
      (node (ref "B1") (pin "5") (pinfunction "5_5") (pintype "bidirectional"))
      (node (ref "JP5") (pin "5") (pinfunction "5_5") (pintype "passive"))
    )
    (net (code "65") (name "Net-(B1-Pad6)") (class "Default")
      (node (ref "B1") (pin "6") (pinfunction "6_6") (pintype "bidirectional"))
      (node (ref "JP5") (pin "4") (pinfunction "4_4") (pintype "passive"))
    )
    (net (code "66") (name "Net-(B1-Pad7)") (class "Default")
      (node (ref "B1") (pin "7") (pinfunction "7_7") (pintype "bidirectional"))
      (node (ref "JP5") (pin "3") (pinfunction "3_3") (pintype "passive"))
    )
    (net (code "67") (name "Net-(B1-Pad8)") (class "Default")
      (node (ref "B1") (pin "8") (pinfunction "8_8") (pintype "bidirectional"))
      (node (ref "JP5") (pin "2") (pinfunction "2_2") (pintype "passive"))
    )
    (net (code "68") (name "Net-(B1-Pad9)") (class "Default")
      (node (ref "B1") (pin "9") (pinfunction "9_9") (pintype "bidirectional"))
      (node (ref "JP5") (pin "1") (pinfunction "1_1") (pintype "passive"))
    )
    (net (code "69") (name "Net-(B1-Pad40)") (class "Default")
      (node (ref "B1") (pin "40") (pinfunction "40_40") (pintype "bidirectional"))
      (node (ref "JP7") (pin "1") (pinfunction "1_1") (pintype "passive"))
    )
    (net (code "70") (name "Net-(B1-Pad41)") (class "Default")
      (node (ref "B1") (pin "41") (pinfunction "41_41") (pintype "bidirectional"))
      (node (ref "JP6") (pin "7") (pinfunction "7_7") (pintype "passive"))
    )
    (net (code "71") (name "Net-(B1-Pad42)") (class "Default")
      (node (ref "B1") (pin "42") (pinfunction "42_42") (pintype "bidirectional"))
      (node (ref "JP7") (pin "2") (pinfunction "2_2") (pintype "passive"))
    )
    (net (code "72") (name "Net-(B1-Pad43)") (class "Default")
      (node (ref "B1") (pin "43") (pinfunction "43_43") (pintype "bidirectional"))
      (node (ref "JP6") (pin "6") (pinfunction "6_6") (pintype "passive"))
    )
    (net (code "73") (name "Net-(B1-Pad44)") (class "Default")
      (node (ref "B1") (pin "44") (pinfunction "44_44") (pintype "bidirectional"))
      (node (ref "JP7") (pin "3") (pinfunction "3_3") (pintype "passive"))
    )
    (net (code "74") (name "Net-(B1-Pad45)") (class "Default")
      (node (ref "B1") (pin "45") (pinfunction "45_45") (pintype "bidirectional"))
      (node (ref "JP6") (pin "5") (pinfunction "5_5") (pintype "passive"))
    )
    (net (code "75") (name "Net-(B1-Pad46)") (class "Default")
      (node (ref "B1") (pin "46") (pinfunction "46_46") (pintype "bidirectional"))
      (node (ref "JP7") (pin "4") (pinfunction "4_4") (pintype "passive"))
    )
    (net (code "76") (name "Net-(B1-Pad47)") (class "Default")
      (node (ref "B1") (pin "47") (pinfunction "47_47") (pintype "bidirectional"))
      (node (ref "JP6") (pin "4") (pinfunction "4_4") (pintype "passive"))
    )
    (net (code "77") (name "Net-(B1-Pad48)") (class "Default")
      (node (ref "B1") (pin "48") (pinfunction "48_48") (pintype "bidirectional"))
      (node (ref "JP7") (pin "5") (pinfunction "5_5") (pintype "passive"))
    )
    (net (code "78") (name "Net-(B1-Pad49)") (class "Default")
      (node (ref "B1") (pin "49") (pinfunction "49_49") (pintype "bidirectional"))
      (node (ref "JP6") (pin "3") (pinfunction "3_3") (pintype "passive"))
    )
    (net (code "79") (name "Net-(B1-PadA0)") (class "Default")
      (node (ref "B1") (pin "A0") (pinfunction "A0_A0") (pintype "bidirectional"))
      (node (ref "JP3") (pin "9") (pinfunction "9_9") (pintype "passive"))
    )
    (net (code "80") (name "Net-(B1-PadA1)") (class "Default")
      (node (ref "B1") (pin "A1") (pinfunction "A1_A1") (pintype "bidirectional"))
      (node (ref "JP3") (pin "8") (pinfunction "8_8") (pintype "passive"))
    )
    (net (code "81") (name "Net-(B1-PadA2)") (class "Default")
      (node (ref "B1") (pin "A2") (pinfunction "A2_A2") (pintype "bidirectional"))
      (node (ref "JP3") (pin "7") (pinfunction "7_7") (pintype "passive"))
    )
    (net (code "82") (name "Net-(B1-PadA3)") (class "Default")
      (node (ref "B1") (pin "A3") (pinfunction "A3_A3") (pintype "bidirectional"))
      (node (ref "JP3") (pin "6") (pinfunction "6_6") (pintype "passive"))
    )
    (net (code "83") (name "Net-(B1-PadA4)") (class "Default")
      (node (ref "B1") (pin "A4") (pinfunction "A4_A4") (pintype "bidirectional"))
      (node (ref "JP3") (pin "5") (pinfunction "5_5") (pintype "passive"))
    )
    (net (code "84") (name "Net-(B1-PadA5)") (class "Default")
      (node (ref "B1") (pin "A5") (pinfunction "A5_A5") (pintype "bidirectional"))
      (node (ref "JP3") (pin "4") (pinfunction "4_4") (pintype "passive"))
    )
    (net (code "85") (name "Net-(B1-PadA6)") (class "Default")
      (node (ref "B1") (pin "A6") (pinfunction "A6_A6") (pintype "bidirectional"))
      (node (ref "JP3") (pin "3") (pinfunction "3_3") (pintype "passive"))
    )
    (net (code "86") (name "Net-(B1-PadA7)") (class "Default")
      (node (ref "B1") (pin "A7") (pinfunction "A7_A7") (pintype "bidirectional"))
      (node (ref "JP3") (pin "2") (pinfunction "2_2") (pintype "passive"))
    )
    (net (code "87") (name "Net-(B1-PadA8)") (class "Default")
      (node (ref "B1") (pin "A8") (pinfunction "A8_A8") (pintype "bidirectional"))
      (node (ref "JP3") (pin "1") (pinfunction "1_1") (pintype "passive"))
    )
    (net (code "88") (name "Net-(B1-PadA11)") (class "Default")
      (node (ref "B1") (pin "A11") (pinfunction "A11_A11") (pintype "bidirectional"))
      (node (ref "JP2") (pin "5") (pinfunction "5_5") (pintype "passive"))
    )
    (net (code "89") (name "Net-(B1-PadA12)") (class "Default")
      (node (ref "B1") (pin "A12") (pinfunction "A12_A12") (pintype "bidirectional"))
      (node (ref "JP2") (pin "4") (pinfunction "4_4") (pintype "passive"))
    )
    (net (code "90") (name "Net-(B1-PadA13)") (class "Default")
      (node (ref "B1") (pin "A13") (pinfunction "A13_A13") (pintype "bidirectional"))
      (node (ref "JP2") (pin "3") (pinfunction "3_3") (pintype "passive"))
    )
    (net (code "91") (name "Net-(B1-PadA14)") (class "Default")
      (node (ref "B1") (pin "A14") (pinfunction "A14_A14") (pintype "bidirectional"))
      (node (ref "JP2") (pin "2") (pinfunction "2_2") (pintype "passive"))
    )
    (net (code "92") (name "Net-(B1-PadA15)") (class "Default")
      (node (ref "B1") (pin "A15") (pinfunction "A15_A15") (pintype "bidirectional"))
      (node (ref "JP2") (pin "1") (pinfunction "1_1") (pintype "passive"))
    )
    (net (code "93") (name "Net-(D1-PadA)") (class "Default")
      (node (ref "D1") (pin "A") (pinfunction "A_A") (pintype "passive"))
      (node (ref "F6") (pin "2") (pinfunction "2_2") (pintype "passive"))
    )
    (net (code "94") (name "Net-(F6-Pad1)") (class "Default")
      (node (ref "F6") (pin "1") (pinfunction "1_1") (pintype "passive"))
      (node (ref "U$3") (pin "P$2") (pinfunction "P$2_P$2") (pintype "bidirectional"))
    )
    (net (code "95") (name "Net-(JP1-Pad1)") (class "Default")
      (node (ref "JP1") (pin "1") (pinfunction "1_1") (pintype "passive"))
      (node (ref "U$1") (pin "D13") (pinfunction "D13_D13") (pintype "bidirectional"))
    )
    (net (code "96") (name "Net-(JP1-Pad2)") (class "Default")
      (node (ref "JP1") (pin "2") (pinfunction "2_2") (pintype "passive"))
      (node (ref "U$1") (pin "D12") (pinfunction "D12_D12") (pintype "bidirectional"))
    )
    (net (code "97") (name "Net-(JP1-Pad3)") (class "Default")
      (node (ref "JP1") (pin "3") (pinfunction "3_3") (pintype "passive"))
      (node (ref "U$1") (pin "D11") (pinfunction "D11_D11") (pintype "bidirectional"))
    )
    (net (code "98") (name "Net-(JP1-Pad4)") (class "Default")
      (node (ref "JP1") (pin "4") (pinfunction "4_4") (pintype "passive"))
      (node (ref "U$1") (pin "D10") (pinfunction "D10_D10") (pintype "bidirectional"))
    )
    (net (code "99") (name "Net-(JP1-Pad5)") (class "Default")
      (node (ref "JP1") (pin "5") (pinfunction "5_5") (pintype "passive"))
      (node (ref "U$1") (pin "D9") (pinfunction "D9_D9") (pintype "bidirectional"))
    )
    (net (code "100") (name "Net-(JP1-Pad6)") (class "Default")
      (node (ref "JP1") (pin "6") (pinfunction "6_6") (pintype "passive"))
      (node (ref "U$1") (pin "D8") (pinfunction "D8_D8") (pintype "bidirectional"))
    )
    (net (code "101") (name "Net-(JP1-Pad7)") (class "Default")
      (node (ref "JP1") (pin "7") (pinfunction "7_7") (pintype "passive"))
      (node (ref "U$1") (pin "D7") (pinfunction "D7_D7") (pintype "bidirectional"))
    )
    (net (code "102") (name "Net-(JP1-Pad8)") (class "Default")
      (node (ref "JP1") (pin "8") (pinfunction "8_8") (pintype "passive"))
      (node (ref "U$1") (pin "D6") (pinfunction "D6_D6") (pintype "bidirectional"))
    )
    (net (code "103") (name "Net-(JP4-Pad1)") (class "Default")
      (node (ref "JP4") (pin "1") (pinfunction "1_1") (pintype "passive"))
      (node (ref "U$1") (pin "A7") (pinfunction "A7_A7") (pintype "bidirectional"))
    )
    (net (code "104") (name "Net-(JP4-Pad2)") (class "Default")
      (node (ref "JP4") (pin "2") (pinfunction "2_2") (pintype "passive"))
      (node (ref "U$1") (pin "A6") (pinfunction "A6_A6") (pintype "bidirectional"))
    )
    (net (code "105") (name "Net-(JP4-Pad3)") (class "Default")
      (node (ref "JP4") (pin "3") (pinfunction "3_3") (pintype "passive"))
      (node (ref "U$1") (pin "A5") (pinfunction "A5_A5") (pintype "bidirectional"))
    )
    (net (code "106") (name "Net-(JP4-Pad4)") (class "Default")
      (node (ref "JP4") (pin "4") (pinfunction "4_4") (pintype "passive"))
      (node (ref "U$1") (pin "A4") (pinfunction "A4_A4") (pintype "bidirectional"))
    )
    (net (code "107") (name "Net-(JP4-Pad5)") (class "Default")
      (node (ref "JP4") (pin "5") (pinfunction "5_5") (pintype "passive"))
      (node (ref "U$1") (pin "A3") (pinfunction "A3_A3") (pintype "bidirectional"))
    )
    (net (code "108") (name "Net-(JP4-Pad6)") (class "Default")
      (node (ref "JP4") (pin "6") (pinfunction "6_6") (pintype "passive"))
      (node (ref "U$1") (pin "A2") (pinfunction "A2_A2") (pintype "bidirectional"))
    )
    (net (code "109") (name "Net-(JP4-Pad7)") (class "Default")
      (node (ref "JP4") (pin "7") (pinfunction "7_7") (pintype "passive"))
      (node (ref "U$1") (pin "A1") (pinfunction "A1_A1") (pintype "bidirectional"))
    )
    (net (code "110") (name "Net-(JP4-Pad8)") (class "Default")
      (node (ref "JP4") (pin "8") (pinfunction "8_8") (pintype "passive"))
      (node (ref "U$1") (pin "A0") (pinfunction "A0_A0") (pintype "bidirectional"))
    )
    (net (code "111") (name "Net-(JP9-Pad1)") (class "Default")
      (node (ref "JP9") (pin "1") (pinfunction "1_1") (pintype "passive"))
      (node (ref "U$1") (pin "RX1") (pinfunction "RX1_RX1") (pintype "bidirectional"))
    )
    (net (code "112") (name "Net-(JP9-Pad2)") (class "Default")
      (node (ref "JP9") (pin "2") (pinfunction "2_2") (pintype "passive"))
      (node (ref "U$1") (pin "TX0") (pinfunction "TX0_TX0") (pintype "bidirectional"))
    )
    (net (code "113") (name "Net-(LED12V-C)") (class "Default")
      (node (ref "LED12V") (pin "K") (pinfunction "C_K") (pintype "passive"))
      (node (ref "R4") (pin "2") (pinfunction "2_2") (pintype "passive"))
    )
    (net (code "114") (name "Net-(LED12V1-C)") (class "Default")
      (node (ref "LED12V1") (pin "K") (pinfunction "C_K") (pintype "passive"))
      (node (ref "R8") (pin "2") (pinfunction "2_2") (pintype "passive"))
    )
    (net (code "115") (name "Net-(LED12V2-C)") (class "Default")
      (node (ref "LED12V2") (pin "K") (pinfunction "C_K") (pintype "passive"))
      (node (ref "R9") (pin "2") (pinfunction "2_2") (pintype "passive"))
    )
    (net (code "116") (name "Net-(LED12V3-C)") (class "Default")
      (node (ref "LED12V3") (pin "K") (pinfunction "C_K") (pintype "passive"))
      (node (ref "R10") (pin "2") (pinfunction "2_2") (pintype "passive"))
    )
    (net (code "117") (name "Net-(LED12V4-C)") (class "Default")
      (node (ref "LED12V4") (pin "K") (pinfunction "C_K") (pintype "passive"))
      (node (ref "R11") (pin "2") (pinfunction "2_2") (pintype "passive"))
    )
    (net (code "118") (name "Net-(LED12V5-C)") (class "Default")
      (node (ref "LED12V5") (pin "K") (pinfunction "C_K") (pintype "passive"))
      (node (ref "R12") (pin "2") (pinfunction "2_2") (pintype "passive"))
    )
    (net (code "119") (name "Net-(LED12V6-C)") (class "Default")
      (node (ref "LED12V6") (pin "K") (pinfunction "C_K") (pintype "passive"))
      (node (ref "R13") (pin "2") (pinfunction "2_2") (pintype "passive"))
    )
    (net (code "120") (name "Net-(LED12V7-C)") (class "Default")
      (node (ref "LED12V7") (pin "K") (pinfunction "C_K") (pintype "passive"))
      (node (ref "R14") (pin "2") (pinfunction "2_2") (pintype "passive"))
    )
    (net (code "121") (name "Net-(LED12V8-C)") (class "Default")
      (node (ref "LED12V8") (pin "K") (pinfunction "C_K") (pintype "passive"))
      (node (ref "R15") (pin "2") (pinfunction "2_2") (pintype "passive"))
    )
    (net (code "122") (name "Net-(LED12V9-C)") (class "Default")
      (node (ref "LED12V9") (pin "K") (pinfunction "C_K") (pintype "passive"))
      (node (ref "R16") (pin "2") (pinfunction "2_2") (pintype "passive"))
    )
    (net (code "123") (name "Net-(LED12V10-C)") (class "Default")
      (node (ref "LED12V10") (pin "K") (pinfunction "C_K") (pintype "passive"))
      (node (ref "R17") (pin "2") (pinfunction "2_2") (pintype "passive"))
    )
    (net (code "124") (name "Net-(LED12V11-C)") (class "Default")
      (node (ref "LED12V11") (pin "K") (pinfunction "C_K") (pintype "passive"))
      (node (ref "R18") (pin "2") (pinfunction "2_2") (pintype "passive"))
    )
    (net (code "125") (name "Net-(LED12V12-C)") (class "Default")
      (node (ref "LED12V12") (pin "K") (pinfunction "C_K") (pintype "passive"))
      (node (ref "R19") (pin "2") (pinfunction "2_2") (pintype "passive"))
    )
    (net (code "126") (name "Net-(LED12V13-C)") (class "Default")
      (node (ref "LED12V13") (pin "K") (pinfunction "C_K") (pintype "passive"))
      (node (ref "R20") (pin "2") (pinfunction "2_2") (pintype "passive"))
    )
    (net (code "127") (name "Net-(LED12V14-C)") (class "Default")
      (node (ref "LED12V14") (pin "K") (pinfunction "C_K") (pintype "passive"))
      (node (ref "R21") (pin "2") (pinfunction "2_2") (pintype "passive"))
    )
    (net (code "128") (name "Net-(LED12V15-C)") (class "Default")
      (node (ref "LED12V15") (pin "K") (pinfunction "C_K") (pintype "passive"))
      (node (ref "R22") (pin "2") (pinfunction "2_2") (pintype "passive"))
    )
    (net (code "129") (name "Net-(LED12V16-C)") (class "Default")
      (node (ref "LED12V16") (pin "K") (pinfunction "C_K") (pintype "passive"))
      (node (ref "R23") (pin "2") (pinfunction "2_2") (pintype "passive"))
    )
    (net (code "130") (name "Net-(LED12V17-C)") (class "Default")
      (node (ref "LED12V17") (pin "K") (pinfunction "C_K") (pintype "passive"))
      (node (ref "R24") (pin "2") (pinfunction "2_2") (pintype "passive"))
    )
    (net (code "131") (name "Net-(LED12V18-C)") (class "Default")
      (node (ref "LED12V18") (pin "K") (pinfunction "C_K") (pintype "passive"))
      (node (ref "R25") (pin "2") (pinfunction "2_2") (pintype "passive"))
    )
    (net (code "132") (name "Net-(LED12V19-C)") (class "Default")
      (node (ref "LED12V19") (pin "K") (pinfunction "C_K") (pintype "passive"))
      (node (ref "R26") (pin "2") (pinfunction "2_2") (pintype "passive"))
    )
    (net (code "133") (name "Net-(LED24V-C)") (class "Default")
      (node (ref "LED24V") (pin "K") (pinfunction "C_K") (pintype "passive"))
      (node (ref "R1") (pin "2") (pinfunction "2_2") (pintype "passive"))
    )
    (net (code "134") (name "Net-(T1-B)") (class "Default")
      (node (ref "R6") (pin "2") (pinfunction "2_2") (pintype "passive"))
      (node (ref "T1") (pin "1") (pinfunction "B_1") (pintype "passive"))
    )
    (net (code "135") (name "Net-(T2-B)") (class "Default")
      (node (ref "R7") (pin "2") (pinfunction "2_2") (pintype "passive"))
      (node (ref "T2") (pin "1") (pinfunction "B_1") (pintype "passive"))
    )
    (net (code "136") (name "PWM.A") (class "Default")
      (node (ref "B1") (pin "13") (pinfunction "13_13") (pintype "bidirectional"))
      (node (ref "DRIVER.1") (pin "2") (pinfunction "2_2") (pintype "passive"))
    )
    (net (code "137") (name "PWM.B") (class "Default")
      (node (ref "B1") (pin "12") (pinfunction "12_12") (pintype "bidirectional"))
      (node (ref "DRIVER.1") (pin "4") (pinfunction "4_4") (pintype "passive"))
    )
    (net (code "138") (name "PWM.C") (class "Default")
      (node (ref "B1") (pin "11") (pinfunction "11_11") (pintype "bidirectional"))
      (node (ref "DRIVER.2") (pin "2") (pinfunction "2_2") (pintype "passive"))
    )
    (net (code "139") (name "PWM.D") (class "Default")
      (node (ref "B1") (pin "10") (pinfunction "10_10") (pintype "bidirectional"))
      (node (ref "DRIVER.2") (pin "4") (pinfunction "4_4") (pintype "passive"))
    )
    (net (code "140") (name "RESET.MEGA") (class "Default")
      (node (ref "B1") (pin "RESET") (pinfunction "~{RESET}_RESET") (pintype "bidirectional"))
      (node (ref "R5") (pin "1") (pinfunction "1_1") (pintype "passive"))
      (node (ref "U$2") (pin "2") (pinfunction "2_2") (pintype "bidirectional"))
    )
    (net (code "141") (name "RX.BLUE") (class "Default")
      (node (ref "BLUETOOTH") (pin "2") (pinfunction "2_2") (pintype "passive"))
      (node (ref "R2") (pin "1") (pinfunction "1_1") (pintype "passive"))
      (node (ref "R3") (pin "2") (pinfunction "2_2") (pintype "passive"))
    )
    (net (code "142") (name "RX.NANO") (class "Default")
      (node (ref "B1") (pin "16") (pinfunction "16(TX2)_16") (pintype "bidirectional"))
      (node (ref "U$1") (pin "D5") (pinfunction "D5_D5") (pintype "bidirectional"))
    )
    (net (code "143") (name "STATE") (class "Default")
      (node (ref "BLUETOOTH") (pin "1") (pinfunction "1_1") (pintype "passive"))
      (node (ref "LED12V18") (pin "A") (pinfunction "A_A") (pintype "passive"))
    )
    (net (code "144") (name "TX.BLUE") (class "Default")
      (node (ref "B1") (pin "15") (pinfunction "15(RX3)_15") (pintype "bidirectional"))
      (node (ref "BLUETOOTH") (pin "3") (pinfunction "3_3") (pintype "passive"))
    )
    (net (code "145") (name "TX.MEGA") (class "Default")
      (node (ref "B1") (pin "14") (pinfunction "14(TX3)_14") (pintype "bidirectional"))
      (node (ref "R2") (pin "2") (pinfunction "2_2") (pintype "passive"))
    )
    (net (code "146") (name "TX.NANO") (class "Default")
      (node (ref "B1") (pin "17") (pinfunction "17(RX2)_17") (pintype "bidirectional"))
      (node (ref "U$1") (pin "D4") (pinfunction "D4_D4") (pintype "bidirectional"))
    )
    (net (code "147") (name "unconnected-(B1-Pad3.3V)") (class "Default")
      (node (ref "B1") (pin "3.3V") (pinfunction "3.3V_3.3V") (pintype "bidirectional"))
    )
    (net (code "148") (name "unconnected-(B1-PadAREF)") (class "Default")
      (node (ref "B1") (pin "AREF") (pinfunction "AREF_AREF") (pintype "bidirectional"))
    )
    (net (code "149") (name "unconnected-(B1-PadIOREF)") (class "Default")
      (node (ref "B1") (pin "IOREF") (pinfunction "IOREF_IOREF") (pintype "bidirectional"))
    )
    (net (code "150") (name "unconnected-(B1-PadSCL)") (class "Default")
      (node (ref "B1") (pin "SCL") (pinfunction "SCL_SCL") (pintype "bidirectional"))
    )
    (net (code "151") (name "unconnected-(B1-PadSDA)") (class "Default")
      (node (ref "B1") (pin "SDA") (pinfunction "SDA_SDA") (pintype "bidirectional"))
    )
    (net (code "152") (name "unconnected-(U$1-PadAREF)") (class "Default")
      (node (ref "U$1") (pin "AREF") (pinfunction "AREF_AREF") (pintype "bidirectional"))
    )
    (net (code "153") (name "unconnected-(U$1-PadRST)") (class "Default")
      (node (ref "U$1") (pin "RST") (pinfunction "RST_RST") (pintype "bidirectional"))
    )
    (net (code "154") (name "unconnected-(U$1-PadRST1)") (class "Default")
      (node (ref "U$1") (pin "RST1") (pinfunction "RST1_RST1") (pintype "bidirectional"))
    )
  )
)
